# transmitterFinal.net
KiCad netlist of a schematic drawn in EAGLE
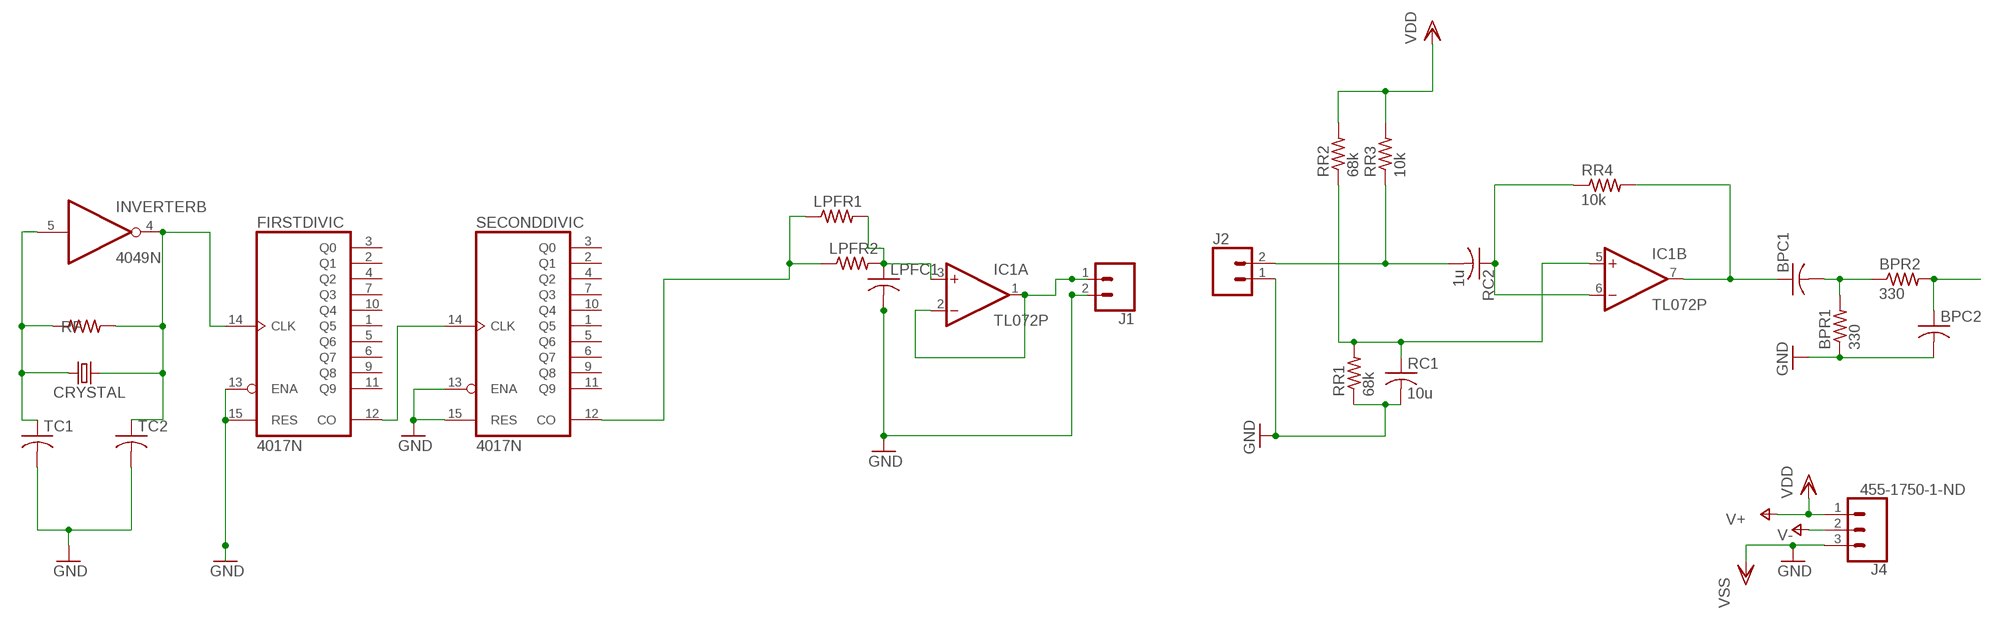
[diagram p0: schematic, sheet 1]

(export (version "E")
  (design (tool "Eeschema 10.0.6"))
  (components
    (comp (ref "BPC1")
      (value "C-US050-025X075")
      (footprint "eagle-import:C050-025X075")
      (libsource (lib "eagle-import") (part "C-US050-025X075"))
    )
    (comp (ref "BPC2")
      (value "C-US050-025X075")
      (footprint "eagle-import:C050-025X075")
      (libsource (lib "eagle-import") (part "C-US050-025X075"))
    )
    (comp (ref "BPR1")
      (value "330")
      (footprint "eagle-import:0309_12")
      (libsource (lib "eagle-import") (part "R-US_0309/12"))
    )
    (comp (ref "BPR2")
      (value "330")
      (footprint "eagle-import:0309_12")
      (libsource (lib "eagle-import") (part "R-US_0309/12"))
    )
    (comp (ref "CRYSTAL")
      (value "CRYSTALHC49U-V")
      (footprint "eagle-import:HC49U-V")
      (libsource (lib "eagle-import") (part "CRYSTALHC49U-V"))
    )
    (comp (ref "FIRSTDIVIC")
      (value "4017N")
      (footprint "eagle-import:DIL16")
      (libsource (lib "eagle-import") (part "4017N"))
    )
    (comp (ref "IC1")
      (value "TL072P")
      (footprint "eagle-import:DIL08")
      (libsource (lib "eagle-import") (part "TL072P"))
    )
    (comp (ref "INVERTER")
      (value "4049N")
      (footprint "eagle-import:DIL16")
      (libsource (lib "eagle-import") (part "4049N"))
    )
    (comp (ref "J1")
      (value "CONN_02")
      (footprint "eagle-import:1X02")
      (libsource (lib "eagle-import") (part "CONN_02"))
    )
    (comp (ref "J2")
      (value "CONN_02")
      (footprint "eagle-import:1X02")
      (libsource (lib "eagle-import") (part "CONN_02"))
    )
    (comp (ref "J4")
      (value "455-1750-1-ND")
      (footprint "eagle-import:1X03")
      (libsource (lib "eagle-import") (part "CONN_03"))
    )
    (comp (ref "LPFC1")
      (value "C-US050-025X075")
      (footprint "eagle-import:C050-025X075")
      (libsource (lib "eagle-import") (part "C-US050-025X075"))
    )
    (comp (ref "LPFR1")
      (value "R-US_0309/12")
      (footprint "eagle-import:0309_12")
      (libsource (lib "eagle-import") (part "R-US_0309/12"))
    )
    (comp (ref "LPFR2")
      (value "R-US_0309/12")
      (footprint "eagle-import:0309_12")
      (libsource (lib "eagle-import") (part "R-US_0309/12"))
    )
    (comp (ref "RC1")
      (value "10u")
      (footprint "eagle-import:C050-025X075")
      (libsource (lib "eagle-import") (part "C-US050-025X075"))
    )
    (comp (ref "RC2")
      (value "1u")
      (footprint "eagle-import:C050-025X075")
      (libsource (lib "eagle-import") (part "C-US050-025X075"))
    )
    (comp (ref "RF")
      (value "R-US_0411/15")
      (footprint "eagle-import:0411_15")
      (libsource (lib "eagle-import") (part "R-US_0411/15"))
    )
    (comp (ref "RR1")
      (value "68k")
      (footprint "eagle-import:0309_12")
      (libsource (lib "eagle-import") (part "R-US_0309/12"))
    )
    (comp (ref "RR2")
      (value "68k")
      (footprint "eagle-import:0309_12")
      (libsource (lib "eagle-import") (part "R-US_0309/12"))
    )
    (comp (ref "RR3")
      (value "10k")
      (footprint "eagle-import:0309_12")
      (libsource (lib "eagle-import") (part "R-US_0309/12"))
    )
    (comp (ref "RR4")
      (value "10k")
      (footprint "eagle-import:0309_12")
      (libsource (lib "eagle-import") (part "R-US_0309/12"))
    )
    (comp (ref "SECONDDIVIC")
      (value "4017N")
      (footprint "eagle-import:DIL16")
      (libsource (lib "eagle-import") (part "4017N"))
    )
    (comp (ref "TC1")
      (value "C-US050-025X075")
      (footprint "eagle-import:C050-025X075")
      (libsource (lib "eagle-import") (part "C-US050-025X075"))
    )
    (comp (ref "TC2")
      (value "C-US050-025X075")
      (footprint "eagle-import:C050-025X075")
      (libsource (lib "eagle-import") (part "C-US050-025X075"))
    )
  )
  (nets
    (net (code "1") (name "GND") (class "Default")
      (node (ref "BPC2") (pin "2") (pinfunction "2_2") (pintype "passive"))
      (node (ref "BPR1") (pin "1") (pinfunction "1_1") (pintype "passive"))
      (node (ref "FIRSTDIVIC") (pin "13") (pinfunction "ENA_13") (pintype "input"))
      (node (ref "FIRSTDIVIC") (pin "15") (pinfunction "RES_15") (pintype "input"))
      (node (ref "J1") (pin "2") (pinfunction "2_2") (pintype "passive"))
      (node (ref "J2") (pin "1") (pinfunction "1_1") (pintype "passive"))
      (node (ref "J4") (pin "3") (pinfunction "3_3") (pintype "passive"))
      (node (ref "LPFC1") (pin "2") (pinfunction "2_2") (pintype "passive"))
      (node (ref "RC1") (pin "2") (pinfunction "2_2") (pintype "passive"))
      (node (ref "RR1") (pin "1") (pinfunction "1_1") (pintype "passive"))
      (node (ref "SECONDDIVIC") (pin "13") (pinfunction "ENA_13") (pintype "input"))
      (node (ref "SECONDDIVIC") (pin "15") (pinfunction "RES_15") (pintype "input"))
      (node (ref "TC1") (pin "2") (pinfunction "2_2") (pintype "passive"))
      (node (ref "TC2") (pin "2") (pinfunction "2_2") (pintype "passive"))
    )
    (net (code "2") (name "Net-(BPC1-Pad2)") (class "Default")
      (node (ref "BPC1") (pin "2") (pinfunction "2_2") (pintype "passive"))
      (node (ref "BPR1") (pin "2") (pinfunction "2_2") (pintype "passive"))
      (node (ref "BPR2") (pin "1") (pinfunction "1_1") (pintype "passive"))
    )
    (net (code "3") (name "Net-(BPC2-Pad1)") (class "Default")
      (node (ref "BPC2") (pin "1") (pinfunction "1_1") (pintype "passive"))
      (node (ref "BPR2") (pin "2") (pinfunction "2_2") (pintype "passive"))
    )
    (net (code "4") (name "Net-(FIRSTDIVICA-CLK)") (class "Default")
      (node (ref "CRYSTAL") (pin "2") (pinfunction "2_2") (pintype "passive"))
      (node (ref "FIRSTDIVIC") (pin "14") (pinfunction "CLK_14") (pintype "input"))
      (node (ref "INVERTER") (pin "4") (pinfunction "O_4") (pintype "output"))
      (node (ref "RF") (pin "2") (pinfunction "2_2") (pintype "passive"))
      (node (ref "TC2") (pin "1") (pinfunction "1_1") (pintype "passive"))
    )
    (net (code "5") (name "Net-(FIRSTDIVICA-CO)") (class "Default")
      (node (ref "FIRSTDIVIC") (pin "12") (pinfunction "CO_12") (pintype "output"))
      (node (ref "SECONDDIVIC") (pin "14") (pinfunction "CLK_14") (pintype "input"))
    )
    (net (code "6") (name "Net-(IC1A-+IN)") (class "Default")
      (node (ref "IC1") (pin "3") (pinfunction "+IN_3") (pintype "input"))
      (node (ref "LPFC1") (pin "1") (pinfunction "1_1") (pintype "passive"))
      (node (ref "LPFR1") (pin "2") (pinfunction "2_2") (pintype "passive"))
      (node (ref "LPFR2") (pin "2") (pinfunction "2_2") (pintype "passive"))
    )
    (net (code "7") (name "Net-(IC1A--IN)") (class "Default")
      (node (ref "IC1") (pin "1") (pinfunction "OUT_1") (pintype "output"))
      (node (ref "IC1") (pin "2") (pinfunction "-IN_2") (pintype "input"))
      (node (ref "J1") (pin "1") (pinfunction "1_1") (pintype "passive"))
    )
    (net (code "8") (name "Net-(IC1B-+IN)") (class "Default")
      (node (ref "IC1") (pin "5") (pinfunction "+IN_5") (pintype "input"))
      (node (ref "RC1") (pin "1") (pinfunction "1_1") (pintype "passive"))
      (node (ref "RR1") (pin "2") (pinfunction "2_2") (pintype "passive"))
      (node (ref "RR2") (pin "1") (pinfunction "1_1") (pintype "passive"))
    )
    (net (code "9") (name "Net-(IC1B--IN)") (class "Default")
      (node (ref "IC1") (pin "6") (pinfunction "-IN_6") (pintype "input"))
      (node (ref "RC2") (pin "1") (pinfunction "1_1") (pintype "passive"))
      (node (ref "RR4") (pin "1") (pinfunction "1_1") (pintype "passive"))
    )
    (net (code "10") (name "Net-(IC1B-OUT)") (class "Default")
      (node (ref "BPC1") (pin "1") (pinfunction "1_1") (pintype "passive"))
      (node (ref "IC1") (pin "7") (pinfunction "OUT_7") (pintype "output"))
      (node (ref "RR4") (pin "2") (pinfunction "2_2") (pintype "passive"))
    )
    (net (code "11") (name "Net-(INVERTERB-I)") (class "Default")
      (node (ref "CRYSTAL") (pin "1") (pinfunction "1_1") (pintype "passive"))
      (node (ref "INVERTER") (pin "5") (pinfunction "I_5") (pintype "input"))
      (node (ref "RF") (pin "1") (pinfunction "1_1") (pintype "passive"))
      (node (ref "TC1") (pin "1") (pinfunction "1_1") (pintype "passive"))
    )
    (net (code "12") (name "Net-(J2-Pad2)") (class "Default")
      (node (ref "J2") (pin "2") (pinfunction "2_2") (pintype "passive"))
      (node (ref "RC2") (pin "2") (pinfunction "2_2") (pintype "passive"))
      (node (ref "RR3") (pin "1") (pinfunction "1_1") (pintype "passive"))
    )
    (net (code "13") (name "Net-(SECONDDIVICA-CO)") (class "Default")
      (node (ref "LPFR1") (pin "1") (pinfunction "1_1") (pintype "passive"))
      (node (ref "LPFR2") (pin "1") (pinfunction "1_1") (pintype "passive"))
      (node (ref "SECONDDIVIC") (pin "12") (pinfunction "CO_12") (pintype "output"))
    )
    (net (code "14") (name "V+") (class "Default")
      (node (ref "J4") (pin "1") (pinfunction "1_1") (pintype "passive"))
      (node (ref "RR2") (pin "2") (pinfunction "2_2") (pintype "passive"))
      (node (ref "RR3") (pin "2") (pinfunction "2_2") (pintype "passive"))
    )
    (net (code "15") (name "V-") (class "Default")
      (node (ref "J4") (pin "2") (pinfunction "2_2") (pintype "passive"))
    )
    (net (code "16") (name "unconnected-(FIRSTDIVICA-Q0-Pad3)") (class "Default")
      (node (ref "FIRSTDIVIC") (pin "3") (pinfunction "Q0_3") (pintype "output"))
    )
    (net (code "17") (name "unconnected-(FIRSTDIVICA-Q1-Pad2)") (class "Default")
      (node (ref "FIRSTDIVIC") (pin "2") (pinfunction "Q1_2") (pintype "output"))
    )
    (net (code "18") (name "unconnected-(FIRSTDIVICA-Q2-Pad4)") (class "Default")
      (node (ref "FIRSTDIVIC") (pin "4") (pinfunction "Q2_4") (pintype "output"))
    )
    (net (code "19") (name "unconnected-(FIRSTDIVICA-Q3-Pad7)") (class "Default")
      (node (ref "FIRSTDIVIC") (pin "7") (pinfunction "Q3_7") (pintype "output"))
    )
    (net (code "20") (name "unconnected-(FIRSTDIVICA-Q4-Pad10)") (class "Default")
      (node (ref "FIRSTDIVIC") (pin "10") (pinfunction "Q4_10") (pintype "output"))
    )
    (net (code "21") (name "unconnected-(FIRSTDIVICA-Q5-Pad1)") (class "Default")
      (node (ref "FIRSTDIVIC") (pin "1") (pinfunction "Q5_1") (pintype "output"))
    )
    (net (code "22") (name "unconnected-(FIRSTDIVICA-Q6-Pad5)") (class "Default")
      (node (ref "FIRSTDIVIC") (pin "5") (pinfunction "Q6_5") (pintype "output"))
    )
    (net (code "23") (name "unconnected-(FIRSTDIVICA-Q7-Pad6)") (class "Default")
      (node (ref "FIRSTDIVIC") (pin "6") (pinfunction "Q7_6") (pintype "output"))
    )
    (net (code "24") (name "unconnected-(FIRSTDIVICA-Q8-Pad9)") (class "Default")
      (node (ref "FIRSTDIVIC") (pin "9") (pinfunction "Q8_9") (pintype "output"))
    )
    (net (code "25") (name "unconnected-(FIRSTDIVICA-Q9-Pad11)") (class "Default")
      (node (ref "FIRSTDIVIC") (pin "11") (pinfunction "Q9_11") (pintype "output"))
    )
    (net (code "26") (name "unconnected-(SECONDDIVICA-Q0-Pad3)") (class "Default")
      (node (ref "SECONDDIVIC") (pin "3") (pinfunction "Q0_3") (pintype "output"))
    )
    (net (code "27") (name "unconnected-(SECONDDIVICA-Q1-Pad2)") (class "Default")
      (node (ref "SECONDDIVIC") (pin "2") (pinfunction "Q1_2") (pintype "output"))
    )
    (net (code "28") (name "unconnected-(SECONDDIVICA-Q2-Pad4)") (class "Default")
      (node (ref "SECONDDIVIC") (pin "4") (pinfunction "Q2_4") (pintype "output"))
    )
    (net (code "29") (name "unconnected-(SECONDDIVICA-Q3-Pad7)") (class "Default")
      (node (ref "SECONDDIVIC") (pin "7") (pinfunction "Q3_7") (pintype "output"))
    )
    (net (code "30") (name "unconnected-(SECONDDIVICA-Q4-Pad10)") (class "Default")
      (node (ref "SECONDDIVIC") (pin "10") (pinfunction "Q4_10") (pintype "output"))
    )
    (net (code "31") (name "unconnected-(SECONDDIVICA-Q5-Pad1)") (class "Default")
      (node (ref "SECONDDIVIC") (pin "1") (pinfunction "Q5_1") (pintype "output"))
    )
    (net (code "32") (name "unconnected-(SECONDDIVICA-Q6-Pad5)") (class "Default")
      (node (ref "SECONDDIVIC") (pin "5") (pinfunction "Q6_5") (pintype "output"))
    )
    (net (code "33") (name "unconnected-(SECONDDIVICA-Q7-Pad6)") (class "Default")
      (node (ref "SECONDDIVIC") (pin "6") (pinfunction "Q7_6") (pintype "output"))
    )
    (net (code "34") (name "unconnected-(SECONDDIVICA-Q8-Pad9)") (class "Default")
      (node (ref "SECONDDIVIC") (pin "9") (pinfunction "Q8_9") (pintype "output"))
    )
    (net (code "35") (name "unconnected-(SECONDDIVICA-Q9-Pad11)") (class "Default")
      (node (ref "SECONDDIVIC") (pin "11") (pinfunction "Q9_11") (pintype "output"))
    )
  )
)
